# design.net
KiCad netlist of a schematic drawn in Altium Designer
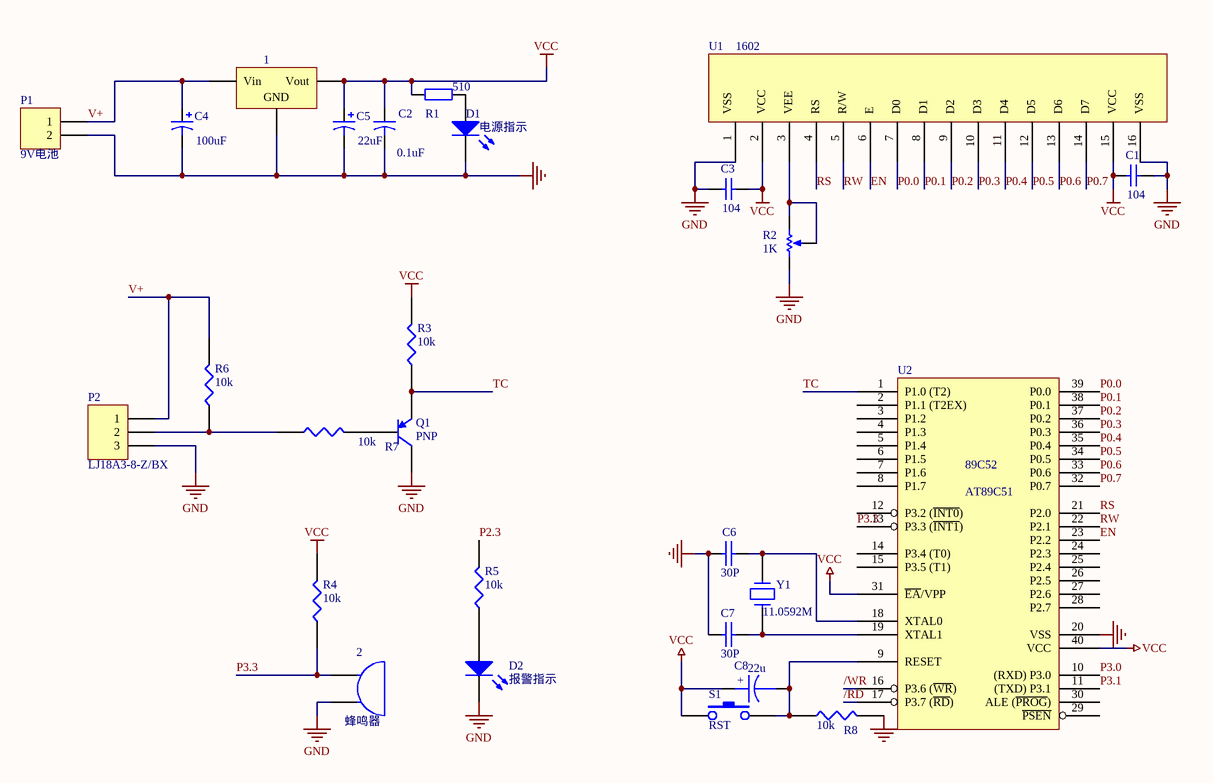
[diagram p0: 金属探测.SchDoc]

(export (version "E")
  (design (tool "Eeschema 10.0.6"))
  (components
    (comp (ref "1")
      (value "~")
      (footprint "SIP-G3/Y2")
      (description "Voltage Regulator")
      (fields (field (name "PUBLISHER") "Altium Limited"))
      (libsource (lib "Miscellaneous Devices") (part "Volt Reg"))
    )
    (comp (ref "2") (value "蜂鸣器") (description "Buzzer") (libsource (lib "*") (part "BUZZER")))
    (comp (ref "C1")
      (value "104")
      (footprint "RAD-0.3")
      (description "Capacitor")
      (fields (field (name "PUBLISHER") "Altium Limited"))
      (libsource (lib "Miscellaneous Devices") (part "Cap"))
    )
    (comp (ref "C2")
      (value "0.1uF")
      (footprint "CAPR5-4X5")
      (description "Capacitor")
      (fields (field (name "PUBLISHER") "Altium Limited"))
      (libsource (lib "Miscellaneous Devices") (part "Cap2"))
    )
    (comp (ref "C3")
      (value "104")
      (footprint "RAD-0.3")
      (description "Capacitor")
      (fields (field (name "PUBLISHER") "Altium Limited"))
      (libsource (lib "Miscellaneous Devices") (part "Cap"))
    )
    (comp (ref "C4")
      (value "100uF")
      (footprint "CC2012-0805")
      (description "Polarized Capacitor (Surface Mount)")
      (fields (field (name "PUBLISHER") "Altium Limited"))
      (libsource (lib "Miscellaneous Devices") (part "Cap Pol3"))
    )
    (comp (ref "C5")
      (value "22uF")
      (footprint "CC2012-0805")
      (description "Polarized Capacitor (Surface Mount)")
      (fields (field (name "PUBLISHER") "Altium Limited"))
      (libsource (lib "Miscellaneous Devices") (part "Cap Pol3"))
    )
    (comp (ref "C6") (value "30P") (description "Capacitor") (libsource (lib "*") (part "CAP")))
    (comp (ref "C7") (value "30P") (description "Capacitor") (libsource (lib "*") (part "CAP")))
    (comp (ref "C8") (value "22u") (description "Capacitor") (libsource (lib "*") (part "CAPACITOR POL")))
    (comp (ref "D1")
      (value "电源指示")
      (footprint "DSO-F2/D6.1")
      (description "Typical RED, GREEN, YELLOW, AMBER GaAs LED")
      (fields (field (name "PUBLISHER") "Altium Limited"))
      (libsource (lib "Miscellaneous Devices") (part "LED2"))
    )
    (comp (ref "D2")
      (value "报警指示")
      (footprint "DSO-F2/D6.1")
      (description "Typical RED, GREEN, YELLOW, AMBER GaAs LED")
      (fields (field (name "PUBLISHER") "Altium Limited"))
      (libsource (lib "Miscellaneous Devices") (part "LED2"))
    )
    (comp (ref "P1")
      (value "9V电池")
      (footprint "HDR1X2")
      (description "Header, 2-Pin")
      (fields (field (name "PUBLISHER") "Altium Limited"))
      (libsource (lib "Miscellaneous Connectors") (part "Header 2"))
    )
    (comp (ref "P2")
      (value "LJ18A3-8-Z/BX")
      (footprint "HDR1X3")
      (description "Header, 3-Pin")
      (fields (field (name "PUBLISHER") "Altium Limited"))
      (libsource (lib "Miscellaneous Connectors") (part "Header 3"))
    )
    (comp (ref "Q1")
      (value "PNP")
      (footprint "SOT-23B_N")
      (description "PNP Bipolar Transistor")
      (fields (field (name "PUBLISHER") "Altium Limited"))
      (libsource (lib "Miscellaneous Devices") (part "PNP"))
    )
    (comp (ref "R1")
      (value "510")
      (footprint "AXIAL-0.4")
      (description "Resistor")
      (fields (field (name "PUBLISHER") "Altium Limited"))
      (libsource (lib "Miscellaneous Devices") (part "Res2"))
    )
    (comp (ref "R2")
      (value "1K")
      (footprint "VR5")
      (description "Potentiometer")
      (fields (field (name "PUBLISHER") "Altium Limited"))
      (libsource (lib "Miscellaneous Devices") (part "RPot"))
    )
    (comp (ref "R3") (value "10k") (libsource (lib "*") (part "RES1")))
    (comp (ref "R4") (value "10k") (libsource (lib "*") (part "RES1")))
    (comp (ref "R5") (value "10k") (libsource (lib "*") (part "RES1")))
    (comp (ref "R6") (value "10k") (libsource (lib "*") (part "RES1")))
    (comp (ref "R7") (value "10k") (libsource (lib "*") (part "RES1")))
    (comp (ref "R8") (value "10k") (libsource (lib "*") (part "RES1")))
    (comp (ref "S1") (value "RST") (libsource (lib "*") (part "SW-PB")))
    (comp (ref "U1") (value "1602") (libsource (lib "signal general") (part "1602")))
    (comp (ref "U2") (value "AT89C51") (libsource (lib "*") (part "89C52")))
    (comp (ref "Y1") (value "11.0592M") (description "Crystal") (libsource (lib "*") (part "CRYSTAL")))
  )
  (nets
    (net (code "1") (name "/EN") (class "Default")
      (node (ref "U1") (pin "6") (pintype "passive"))
      (node (ref "U2") (pin "23") (pinfunction "P2.2_23") (pintype "passive"))
    )
    (net (code "2") (name "/P0.0") (class "Default")
      (node (ref "U1") (pin "7") (pintype "passive"))
      (node (ref "U2") (pin "39") (pinfunction "P0.0_39") (pintype "passive"))
    )
    (net (code "3") (name "/P0.1") (class "Default")
      (node (ref "U1") (pin "8") (pintype "passive"))
      (node (ref "U2") (pin "38") (pinfunction "P0.1_38") (pintype "passive"))
    )
    (net (code "4") (name "/P0.2") (class "Default")
      (node (ref "U1") (pin "9") (pintype "passive"))
      (node (ref "U2") (pin "37") (pinfunction "P0.2_37") (pintype "passive"))
    )
    (net (code "5") (name "/P0.3") (class "Default")
      (node (ref "U1") (pin "10") (pintype "passive"))
      (node (ref "U2") (pin "36") (pinfunction "P0.3_36") (pintype "passive"))
    )
    (net (code "6") (name "/P0.4") (class "Default")
      (node (ref "U1") (pin "11") (pintype "passive"))
      (node (ref "U2") (pin "35") (pinfunction "P0.4_35") (pintype "passive"))
    )
    (net (code "7") (name "/P0.5") (class "Default")
      (node (ref "U1") (pin "12") (pintype "passive"))
      (node (ref "U2") (pin "34") (pinfunction "P0.5_34") (pintype "passive"))
    )
    (net (code "8") (name "/P0.6") (class "Default")
      (node (ref "U1") (pin "13") (pintype "passive"))
      (node (ref "U2") (pin "33") (pinfunction "P0.6_33") (pintype "passive"))
    )
    (net (code "9") (name "/P0.7") (class "Default")
      (node (ref "U1") (pin "14") (pintype "passive"))
      (node (ref "U2") (pin "32") (pinfunction "P0.7_32") (pintype "passive"))
    )
    (net (code "10") (name "/P2.3") (class "Default")
      (node (ref "R5") (pin "2") (pinfunction "2_2") (pintype "passive"))
    )
    (net (code "11") (name "/P3.0") (class "Default")
      (node (ref "U2") (pin "10") (pinfunction "(RXD)_P3.0_10") (pintype "passive"))
    )
    (net (code "12") (name "/P3.1") (class "Default")
      (node (ref "U2") (pin "11") (pinfunction "(TXD)_P3.1_11") (pintype "passive"))
    )
    (net (code "13") (name "/P3.3") (class "Default")
      (node (ref "2") (pin "1") (pinfunction "A_1") (pintype "passive"))
      (node (ref "R4") (pin "1") (pinfunction "1_1") (pintype "passive"))
      (node (ref "U2") (pin "13") (pinfunction "P3.3_(~{INT1})_13") (pintype "passive"))
    )
    (net (code "14") (name "/RS") (class "Default")
      (node (ref "U1") (pin "4") (pintype "passive"))
      (node (ref "U2") (pin "21") (pinfunction "P2.0_21") (pintype "passive"))
    )
    (net (code "15") (name "/RW") (class "Default")
      (node (ref "U1") (pin "5") (pintype "passive"))
      (node (ref "U2") (pin "22") (pinfunction "P2.1_22") (pintype "passive"))
    )
    (net (code "16") (name "/TC") (class "Default")
      (node (ref "Q1") (pin "3") (pinfunction "E_3") (pintype "passive"))
      (node (ref "R3") (pin "1") (pinfunction "1_1") (pintype "passive"))
      (node (ref "U2") (pin "1") (pinfunction "P1.0_(T2)_1") (pintype "passive"))
    )
    (net (code "17") (name "/V+") (class "Default")
      (node (ref "1") (pin "1") (pinfunction "Vin_1") (pintype "passive"))
      (node (ref "C4") (pin "1") (pinfunction "1_1") (pintype "passive"))
      (node (ref "P1") (pin "1") (pinfunction "1_1") (pintype "passive"))
      (node (ref "P2") (pin "1") (pinfunction "1_1") (pintype "passive"))
      (node (ref "R6") (pin "2") (pinfunction "2_2") (pintype "passive"))
    )
    (net (code "18") (name "/{slash}RD") (class "Default")
      (node (ref "U2") (pin "17") (pinfunction "P3.7_(~{RD})_17") (pintype "passive"))
    )
    (net (code "19") (name "/{slash}WR") (class "Default")
      (node (ref "U2") (pin "16") (pinfunction "P3.6_(~{WR})_16") (pintype "passive"))
    )
    (net (code "20") (name "GND") (class "Default")
      (node (ref "1") (pin "2") (pinfunction "GND_2") (pintype "passive"))
      (node (ref "2") (pin "2") (pinfunction "B_2") (pintype "passive"))
      (node (ref "C1") (pin "2") (pinfunction "2_2") (pintype "passive"))
      (node (ref "C2") (pin "2") (pinfunction "2_2") (pintype "passive"))
      (node (ref "C3") (pin "1") (pinfunction "1_1") (pintype "passive"))
      (node (ref "C4") (pin "2") (pinfunction "2_2") (pintype "passive"))
      (node (ref "C5") (pin "2") (pinfunction "2_2") (pintype "passive"))
      (node (ref "C6") (pin "1") (pinfunction "1_1") (pintype "passive"))
      (node (ref "C7") (pin "1") (pinfunction "1_1") (pintype "passive"))
      (node (ref "D1") (pin "2") (pinfunction "K_2") (pintype "passive"))
      (node (ref "D2") (pin "2") (pinfunction "K_2") (pintype "passive"))
      (node (ref "P1") (pin "2") (pinfunction "2_2") (pintype "passive"))
      (node (ref "P2") (pin "3") (pinfunction "3_3") (pintype "passive"))
      (node (ref "Q1") (pin "1") (pinfunction "C_1") (pintype "passive"))
      (node (ref "R2") (pin "1") (pinfunction "TOP_1") (pintype "passive"))
      (node (ref "R8") (pin "2") (pinfunction "2_2") (pintype "passive"))
      (node (ref "U1") (pin "1") (pintype "passive"))
      (node (ref "U1") (pin "16") (pintype "passive"))
      (node (ref "U2") (pin "20") (pinfunction "VSS_20") (pintype "passive"))
    )
    (net (code "21") (name "Net-(D1-A)") (class "Default")
      (node (ref "D1") (pin "1") (pinfunction "A_1") (pintype "passive"))
      (node (ref "R1") (pin "1") (pinfunction "1_1") (pintype "passive"))
    )
    (net (code "22") (name "Net-(D2-A)") (class "Default")
      (node (ref "D2") (pin "1") (pinfunction "A_1") (pintype "passive"))
      (node (ref "R5") (pin "1") (pinfunction "1_1") (pintype "passive"))
    )
    (net (code "23") (name "Net-(P2-Pad2)") (class "Default")
      (node (ref "P2") (pin "2") (pinfunction "2_2") (pintype "passive"))
      (node (ref "R6") (pin "1") (pinfunction "1_1") (pintype "passive"))
      (node (ref "R7") (pin "1") (pinfunction "1_1") (pintype "passive"))
    )
    (net (code "24") (name "Net-(Q1-B)") (class "Default")
      (node (ref "Q1") (pin "2") (pinfunction "B_2") (pintype "passive"))
      (node (ref "R7") (pin "2") (pinfunction "2_2") (pintype "passive"))
    )
    (net (code "25") (name "Net-(R2-BOT)") (class "Default")
      (node (ref "R2") (pin "2") (pinfunction "BOT_2") (pintype "passive"))
      (node (ref "R2") (pin "3") (pinfunction "TAP_3") (pintype "passive"))
      (node (ref "U1") (pin "3") (pintype "passive"))
    )
    (net (code "26") (name "Net-(U2-RESET)") (class "Default")
      (node (ref "C8") (pin "2") (pinfunction "2_2") (pintype "passive"))
      (node (ref "R8") (pin "1") (pinfunction "1_1") (pintype "passive"))
      (node (ref "S1") (pin "2") (pinfunction "2_2") (pintype "passive"))
      (node (ref "U2") (pin "9") (pinfunction "RESET_9") (pintype "passive"))
    )
    (net (code "27") (name "Net-(U2-XTAL0)") (class "Default")
      (node (ref "C6") (pin "2") (pinfunction "2_2") (pintype "passive"))
      (node (ref "U2") (pin "18") (pinfunction "XTAL0_18") (pintype "passive"))
      (node (ref "Y1") (pin "2") (pinfunction "2_2") (pintype "passive"))
    )
    (net (code "28") (name "Net-(U2-XTAL1)") (class "Default")
      (node (ref "C7") (pin "2") (pinfunction "2_2") (pintype "passive"))
      (node (ref "U2") (pin "19") (pinfunction "XTAL1_19") (pintype "passive"))
      (node (ref "Y1") (pin "1") (pinfunction "1_1") (pintype "passive"))
    )
    (net (code "29") (name "VCC") (class "Default")
      (node (ref "1") (pin "3") (pinfunction "Vout_3") (pintype "passive"))
      (node (ref "C1") (pin "1") (pinfunction "1_1") (pintype "passive"))
      (node (ref "C2") (pin "1") (pinfunction "1_1") (pintype "passive"))
      (node (ref "C3") (pin "2") (pinfunction "2_2") (pintype "passive"))
      (node (ref "C5") (pin "1") (pinfunction "1_1") (pintype "passive"))
      (node (ref "C8") (pin "1") (pinfunction "1_1") (pintype "passive"))
      (node (ref "R1") (pin "2") (pinfunction "2_2") (pintype "passive"))
      (node (ref "R3") (pin "2") (pinfunction "2_2") (pintype "passive"))
      (node (ref "R4") (pin "2") (pinfunction "2_2") (pintype "passive"))
      (node (ref "S1") (pin "1") (pinfunction "1_1") (pintype "passive"))
      (node (ref "U1") (pin "15") (pintype "passive"))
      (node (ref "U1") (pin "2") (pintype "passive"))
      (node (ref "U2") (pin "31") (pinfunction "~{EA}/VPP_31") (pintype "passive"))
      (node (ref "U2") (pin "40") (pinfunction "VCC_40") (pintype "passive"))
    )
    (net (code "30") (name "unconnected-(U2-ALE_(~{PROG})-Pad30)") (class "Default")
      (node (ref "U2") (pin "30") (pinfunction "ALE_(~{PROG})_30") (pintype "passive"))
    )
    (net (code "31") (name "unconnected-(U2-P1.1_(T2EX)-Pad2)") (class "Default")
      (node (ref "U2") (pin "2") (pinfunction "P1.1_(T2EX)_2") (pintype "passive"))
    )
    (net (code "32") (name "unconnected-(U2-P1.2-Pad3)") (class "Default")
      (node (ref "U2") (pin "3") (pinfunction "P1.2_3") (pintype "passive"))
    )
    (net (code "33") (name "unconnected-(U2-P1.3-Pad4)") (class "Default")
      (node (ref "U2") (pin "4") (pinfunction "P1.3_4") (pintype "passive"))
    )
    (net (code "34") (name "unconnected-(U2-P1.4-Pad5)") (class "Default")
      (node (ref "U2") (pin "5") (pinfunction "P1.4_5") (pintype "passive"))
    )
    (net (code "35") (name "unconnected-(U2-P1.5-Pad6)") (class "Default")
      (node (ref "U2") (pin "6") (pinfunction "P1.5_6") (pintype "passive"))
    )
    (net (code "36") (name "unconnected-(U2-P1.6-Pad7)") (class "Default")
      (node (ref "U2") (pin "7") (pinfunction "P1.6_7") (pintype "passive"))
    )
    (net (code "37") (name "unconnected-(U2-P1.7-Pad8)") (class "Default")
      (node (ref "U2") (pin "8") (pinfunction "P1.7_8") (pintype "passive"))
    )
    (net (code "38") (name "unconnected-(U2-P2.3-Pad24)") (class "Default")
      (node (ref "U2") (pin "24") (pinfunction "P2.3_24") (pintype "passive"))
    )
    (net (code "39") (name "unconnected-(U2-P2.4-Pad25)") (class "Default")
      (node (ref "U2") (pin "25") (pinfunction "P2.4_25") (pintype "passive"))
    )
    (net (code "40") (name "unconnected-(U2-P2.5-Pad26)") (class "Default")
      (node (ref "U2") (pin "26") (pinfunction "P2.5_26") (pintype "passive"))
    )
    (net (code "41") (name "unconnected-(U2-P2.6-Pad27)") (class "Default")
      (node (ref "U2") (pin "27") (pinfunction "P2.6_27") (pintype "passive"))
    )
    (net (code "42") (name "unconnected-(U2-P2.7-Pad28)") (class "Default")
      (node (ref "U2") (pin "28") (pinfunction "P2.7_28") (pintype "passive"))
    )
    (net (code "43") (name "unconnected-(U2-P3.2_(~{INT0})-Pad12)") (class "Default")
      (node (ref "U2") (pin "12") (pinfunction "P3.2_(~{INT0})_12") (pintype "passive"))
    )
    (net (code "44") (name "unconnected-(U2-P3.4_(T0)-Pad14)") (class "Default")
      (node (ref "U2") (pin "14") (pinfunction "P3.4_(T0)_14") (pintype "passive"))
    )
    (net (code "45") (name "unconnected-(U2-P3.5_(T1)-Pad15)") (class "Default")
      (node (ref "U2") (pin "15") (pinfunction "P3.5_(T1)_15") (pintype "passive"))
    )
    (net (code "46") (name "unconnected-(U2-~{PSEN}-Pad29)") (class "Default")
      (node (ref "U2") (pin "29") (pinfunction "~{PSEN}_29") (pintype "passive"))
    )
  )
)
